# MIC.net
KiCad netlist of a schematic drawn in Altium Designer
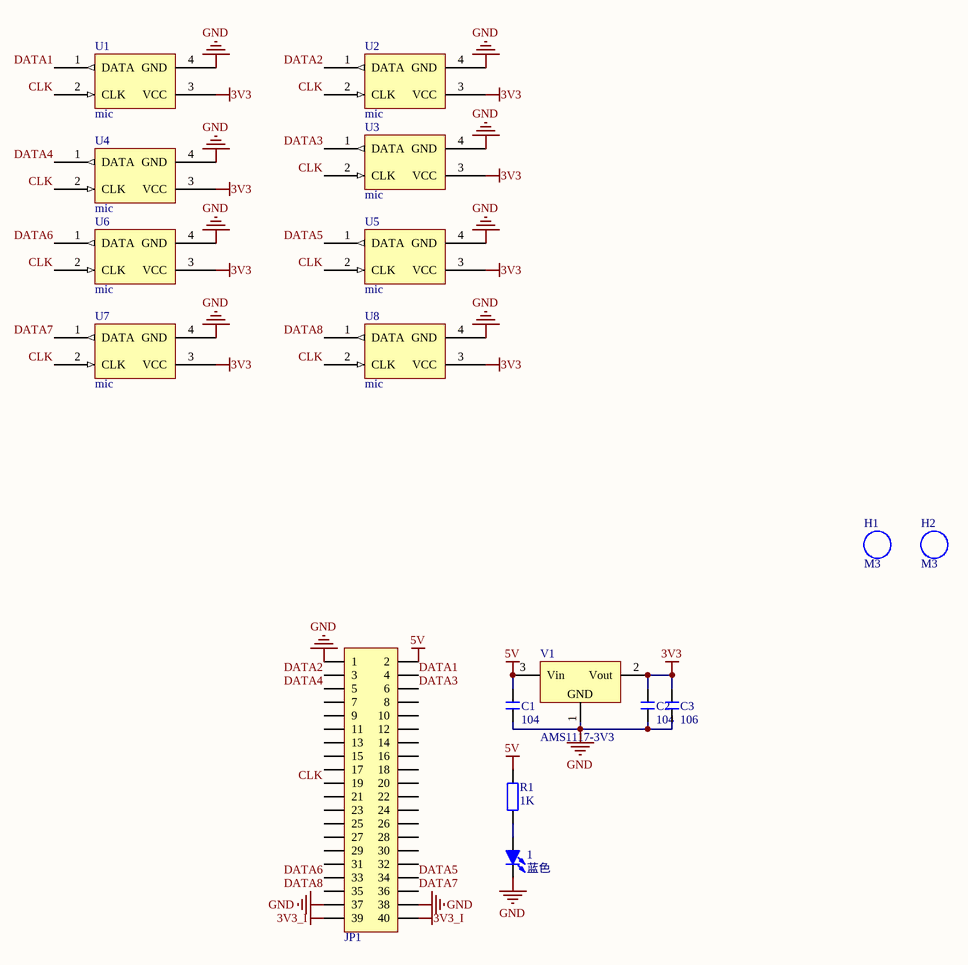
[diagram p0: MIC.SchDoc]

(export (version "E")
  (design (tool "Eeschema 10.0.6"))
  (components
    (comp (ref "1")
      (value "蓝色")
      (footprint "LED 0603B")
      (description "贴片LED")
      (fields (field (name "版权归属") "源创客"))
      (libsource (lib "9.1   - LED") (part "LED-SMD"))
    )
    (comp (ref "C1")
      (value "104")
      (footprint "C 0603_L")
      (description "无极性贴片电容")
      (fields (field (name "版权归属") "源创客"))
      (libsource (lib "3.1   - 电阻-电容-电感") (part "C"))
    )
    (comp (ref "C2")
      (value "104")
      (footprint "C 0603_L")
      (description "无极性贴片电容")
      (fields (field (name "版权归属") "源创客"))
      (libsource (lib "3.1   - 电阻-电容-电感") (part "C"))
    )
    (comp (ref "C3")
      (value "106")
      (footprint "C 0805_M")
      (description "无极性贴片电容")
      (fields (field (name "版权归属") "源创客"))
      (libsource (lib "3.1   - 电阻-电容-电感") (part "C"))
    )
    (comp (ref "H1")
      (value "M3")
      (footprint "M3 125X200")
      (description "铜柱孔")
      (fields (field (name "版权归属") "源创客"))
      (libsource (lib "15.1 - 未分类器件") (part "M3"))
    )
    (comp (ref "H2")
      (value "M3")
      (footprint "M3 125X200")
      (description "铜柱孔")
      (fields (field (name "版权归属") "源创客"))
      (libsource (lib "15.1 - 未分类器件") (part "M3"))
    )
    (comp (ref "JP1")
      (value "Header 2X11")
      (footprint "HDR2.54-LI-2x20P")
      (description "20*2P接插件")
      (fields (field (name "版权归属") "源创客"))
      (libsource (lib "4.5   - 接插件-脚距2.54") (part "Header 20X2"))
    )
    (comp (ref "R1")
      (value "1K")
      (footprint "R 0603_L")
      (description "贴片电阻")
      (fields (field (name "版权归属") "源创客"))
      (libsource (lib "3.1   - 电阻-电容-电感") (part "R"))
    )
    (comp (ref "U1") (value "mic") (footprint "SDM6601") (libsource (lib "MIC") (part "SDM6601P")))
    (comp (ref "U2") (value "mic") (footprint "SDM6601") (libsource (lib "MIC") (part "SDM6601P")))
    (comp (ref "U3") (value "mic") (footprint "SDM6601") (libsource (lib "MIC") (part "SDM6601P")))
    (comp (ref "U4") (value "mic") (footprint "SDM6601") (libsource (lib "MIC") (part "SDM6601P")))
    (comp (ref "U5") (value "mic") (footprint "SDM6601") (libsource (lib "MIC") (part "SDM6601P")))
    (comp (ref "U6") (value "mic") (footprint "SDM6601") (libsource (lib "MIC") (part "SDM6601P")))
    (comp (ref "U7") (value "mic") (footprint "SDM6601") (libsource (lib "MIC") (part "SDM6601P")))
    (comp (ref "U8") (value "mic") (footprint "SDM6601") (libsource (lib "MIC") (part "SDM6601P")))
    (comp (ref "V1")
      (value "AMS1117-3V3")
      (footprint "SOT223_L")
      (description "三端稳压芯片")
      (fields (field (name "版权归属") "源创客"))
      (libsource (lib "1.3   - 电源类芯片") (part "AMS1117"))
    )
  )
  (nets
    (net (code "1") (name "/CLK") (class "Default")
      (node (ref "JP1") (pin "19") (pinfunction "19_19") (pintype "passive"))
      (node (ref "U1") (pin "2") (pinfunction "CLK_2") (pintype "input"))
      (node (ref "U2") (pin "2") (pinfunction "CLK_2") (pintype "input"))
      (node (ref "U3") (pin "2") (pinfunction "CLK_2") (pintype "input"))
      (node (ref "U4") (pin "2") (pinfunction "CLK_2") (pintype "input"))
      (node (ref "U5") (pin "2") (pinfunction "CLK_2") (pintype "input"))
      (node (ref "U6") (pin "2") (pinfunction "CLK_2") (pintype "input"))
      (node (ref "U7") (pin "2") (pinfunction "CLK_2") (pintype "input"))
      (node (ref "U8") (pin "2") (pinfunction "CLK_2") (pintype "input"))
    )
    (net (code "2") (name "/DATA1") (class "Default")
      (node (ref "JP1") (pin "4") (pinfunction "4_4") (pintype "passive"))
      (node (ref "U1") (pin "1") (pinfunction "DATA_1") (pintype "output"))
    )
    (net (code "3") (name "/DATA2") (class "Default")
      (node (ref "JP1") (pin "3") (pinfunction "3_3") (pintype "passive"))
      (node (ref "U2") (pin "1") (pinfunction "DATA_1") (pintype "output"))
    )
    (net (code "4") (name "/DATA3") (class "Default")
      (node (ref "JP1") (pin "6") (pinfunction "6_6") (pintype "passive"))
      (node (ref "U3") (pin "1") (pinfunction "DATA_1") (pintype "output"))
    )
    (net (code "5") (name "/DATA4") (class "Default")
      (node (ref "JP1") (pin "5") (pinfunction "5_5") (pintype "passive"))
      (node (ref "U4") (pin "1") (pinfunction "DATA_1") (pintype "output"))
    )
    (net (code "6") (name "/DATA5") (class "Default")
      (node (ref "JP1") (pin "34") (pinfunction "34_34") (pintype "passive"))
      (node (ref "U5") (pin "1") (pinfunction "DATA_1") (pintype "output"))
    )
    (net (code "7") (name "/DATA6") (class "Default")
      (node (ref "JP1") (pin "33") (pinfunction "33_33") (pintype "passive"))
      (node (ref "U6") (pin "1") (pinfunction "DATA_1") (pintype "output"))
    )
    (net (code "8") (name "/DATA7") (class "Default")
      (node (ref "JP1") (pin "36") (pinfunction "36_36") (pintype "passive"))
      (node (ref "U7") (pin "1") (pinfunction "DATA_1") (pintype "output"))
    )
    (net (code "9") (name "/DATA8") (class "Default")
      (node (ref "JP1") (pin "35") (pinfunction "35_35") (pintype "passive"))
      (node (ref "U8") (pin "1") (pinfunction "DATA_1") (pintype "output"))
    )
    (net (code "10") (name "3V3") (class "Default")
      (node (ref "C2") (pin "1") (pinfunction "1_1") (pintype "passive"))
      (node (ref "C3") (pin "1") (pinfunction "1_1") (pintype "passive"))
      (node (ref "U1") (pin "3") (pinfunction "VCC_3") (pintype "power_in"))
      (node (ref "U2") (pin "3") (pinfunction "VCC_3") (pintype "power_in"))
      (node (ref "U3") (pin "3") (pinfunction "VCC_3") (pintype "power_in"))
      (node (ref "U4") (pin "3") (pinfunction "VCC_3") (pintype "power_in"))
      (node (ref "U5") (pin "3") (pinfunction "VCC_3") (pintype "power_in"))
      (node (ref "U6") (pin "3") (pinfunction "VCC_3") (pintype "power_in"))
      (node (ref "U7") (pin "3") (pinfunction "VCC_3") (pintype "power_in"))
      (node (ref "U8") (pin "3") (pinfunction "VCC_3") (pintype "power_in"))
      (node (ref "V1") (pin "2") (pinfunction "Vout_2") (pintype "passive"))
    )
    (net (code "11") (name "3V3_I") (class "Default")
      (node (ref "JP1") (pin "39") (pinfunction "39_39") (pintype "passive"))
      (node (ref "JP1") (pin "40") (pinfunction "40_40") (pintype "passive"))
    )
    (net (code "12") (name "5V") (class "Default")
      (node (ref "C1") (pin "1") (pinfunction "1_1") (pintype "passive"))
      (node (ref "JP1") (pin "2") (pinfunction "2_2") (pintype "passive"))
      (node (ref "R1") (pin "1") (pinfunction "1_1") (pintype "passive"))
      (node (ref "V1") (pin "3") (pinfunction "Vin_3") (pintype "passive"))
    )
    (net (code "13") (name "GND") (class "Default")
      (node (ref "1") (pin "2") (pinfunction "K_2") (pintype "passive"))
      (node (ref "C1") (pin "2") (pinfunction "2_2") (pintype "passive"))
      (node (ref "C2") (pin "2") (pinfunction "2_2") (pintype "passive"))
      (node (ref "C3") (pin "2") (pinfunction "2_2") (pintype "passive"))
      (node (ref "JP1") (pin "1") (pinfunction "1_1") (pintype "passive"))
      (node (ref "JP1") (pin "37") (pinfunction "37_37") (pintype "passive"))
      (node (ref "JP1") (pin "38") (pinfunction "38_38") (pintype "passive"))
      (node (ref "U1") (pin "4") (pinfunction "GND_4") (pintype "power_in"))
      (node (ref "U2") (pin "4") (pinfunction "GND_4") (pintype "power_in"))
      (node (ref "U3") (pin "4") (pinfunction "GND_4") (pintype "power_in"))
      (node (ref "U4") (pin "4") (pinfunction "GND_4") (pintype "power_in"))
      (node (ref "U5") (pin "4") (pinfunction "GND_4") (pintype "power_in"))
      (node (ref "U6") (pin "4") (pinfunction "GND_4") (pintype "power_in"))
      (node (ref "U7") (pin "4") (pinfunction "GND_4") (pintype "power_in"))
      (node (ref "U8") (pin "4") (pinfunction "GND_4") (pintype "power_in"))
      (node (ref "V1") (pin "1") (pinfunction "GND_1") (pintype "passive"))
    )
    (net (code "14") (name "Net-(1-A)") (class "Default")
      (node (ref "1") (pin "1") (pinfunction "A_1") (pintype "passive"))
      (node (ref "R1") (pin "2") (pinfunction "2_2") (pintype "passive"))
    )
    (net (code "15") (name "unconnected-(JP1-Pad7)") (class "Default")
      (node (ref "JP1") (pin "7") (pinfunction "7_7") (pintype "passive"))
    )
    (net (code "16") (name "unconnected-(JP1-Pad8)") (class "Default")
      (node (ref "JP1") (pin "8") (pinfunction "8_8") (pintype "passive"))
    )
    (net (code "17") (name "unconnected-(JP1-Pad9)") (class "Default")
      (node (ref "JP1") (pin "9") (pinfunction "9_9") (pintype "passive"))
    )
    (net (code "18") (name "unconnected-(JP1-Pad10)") (class "Default")
      (node (ref "JP1") (pin "10") (pinfunction "10_10") (pintype "passive"))
    )
    (net (code "19") (name "unconnected-(JP1-Pad11)") (class "Default")
      (node (ref "JP1") (pin "11") (pinfunction "11_11") (pintype "passive"))
    )
    (net (code "20") (name "unconnected-(JP1-Pad12)") (class "Default")
      (node (ref "JP1") (pin "12") (pinfunction "12_12") (pintype "passive"))
    )
    (net (code "21") (name "unconnected-(JP1-Pad13)") (class "Default")
      (node (ref "JP1") (pin "13") (pinfunction "13_13") (pintype "passive"))
    )
    (net (code "22") (name "unconnected-(JP1-Pad14)") (class "Default")
      (node (ref "JP1") (pin "14") (pinfunction "14_14") (pintype "passive"))
    )
    (net (code "23") (name "unconnected-(JP1-Pad15)") (class "Default")
      (node (ref "JP1") (pin "15") (pinfunction "15_15") (pintype "passive"))
    )
    (net (code "24") (name "unconnected-(JP1-Pad16)") (class "Default")
      (node (ref "JP1") (pin "16") (pinfunction "16_16") (pintype "passive"))
    )
    (net (code "25") (name "unconnected-(JP1-Pad17)") (class "Default")
      (node (ref "JP1") (pin "17") (pinfunction "17_17") (pintype "passive"))
    )
    (net (code "26") (name "unconnected-(JP1-Pad18)") (class "Default")
      (node (ref "JP1") (pin "18") (pinfunction "18_18") (pintype "passive"))
    )
    (net (code "27") (name "unconnected-(JP1-Pad20)") (class "Default")
      (node (ref "JP1") (pin "20") (pinfunction "20_20") (pintype "passive"))
    )
    (net (code "28") (name "unconnected-(JP1-Pad21)") (class "Default")
      (node (ref "JP1") (pin "21") (pinfunction "21_21") (pintype "passive"))
    )
    (net (code "29") (name "unconnected-(JP1-Pad22)") (class "Default")
      (node (ref "JP1") (pin "22") (pinfunction "22_22") (pintype "passive"))
    )
    (net (code "30") (name "unconnected-(JP1-Pad23)") (class "Default")
      (node (ref "JP1") (pin "23") (pinfunction "23_23") (pintype "passive"))
    )
    (net (code "31") (name "unconnected-(JP1-Pad24)") (class "Default")
      (node (ref "JP1") (pin "24") (pinfunction "24_24") (pintype "passive"))
    )
    (net (code "32") (name "unconnected-(JP1-Pad25)") (class "Default")
      (node (ref "JP1") (pin "25") (pinfunction "25_25") (pintype "passive"))
    )
    (net (code "33") (name "unconnected-(JP1-Pad26)") (class "Default")
      (node (ref "JP1") (pin "26") (pinfunction "26_26") (pintype "passive"))
    )
    (net (code "34") (name "unconnected-(JP1-Pad27)") (class "Default")
      (node (ref "JP1") (pin "27") (pinfunction "27_27") (pintype "passive"))
    )
    (net (code "35") (name "unconnected-(JP1-Pad28)") (class "Default")
      (node (ref "JP1") (pin "28") (pinfunction "28_28") (pintype "passive"))
    )
    (net (code "36") (name "unconnected-(JP1-Pad29)") (class "Default")
      (node (ref "JP1") (pin "29") (pinfunction "29_29") (pintype "passive"))
    )
    (net (code "37") (name "unconnected-(JP1-Pad30)") (class "Default")
      (node (ref "JP1") (pin "30") (pinfunction "30_30") (pintype "passive"))
    )
    (net (code "38") (name "unconnected-(JP1-Pad31)") (class "Default")
      (node (ref "JP1") (pin "31") (pinfunction "31_31") (pintype "passive"))
    )
    (net (code "39") (name "unconnected-(JP1-Pad32)") (class "Default")
      (node (ref "JP1") (pin "32") (pinfunction "32_32") (pintype "passive"))
    )
  )
)
